# 11_ESP.net
KiCad netlist of a schematic drawn in EAGLE
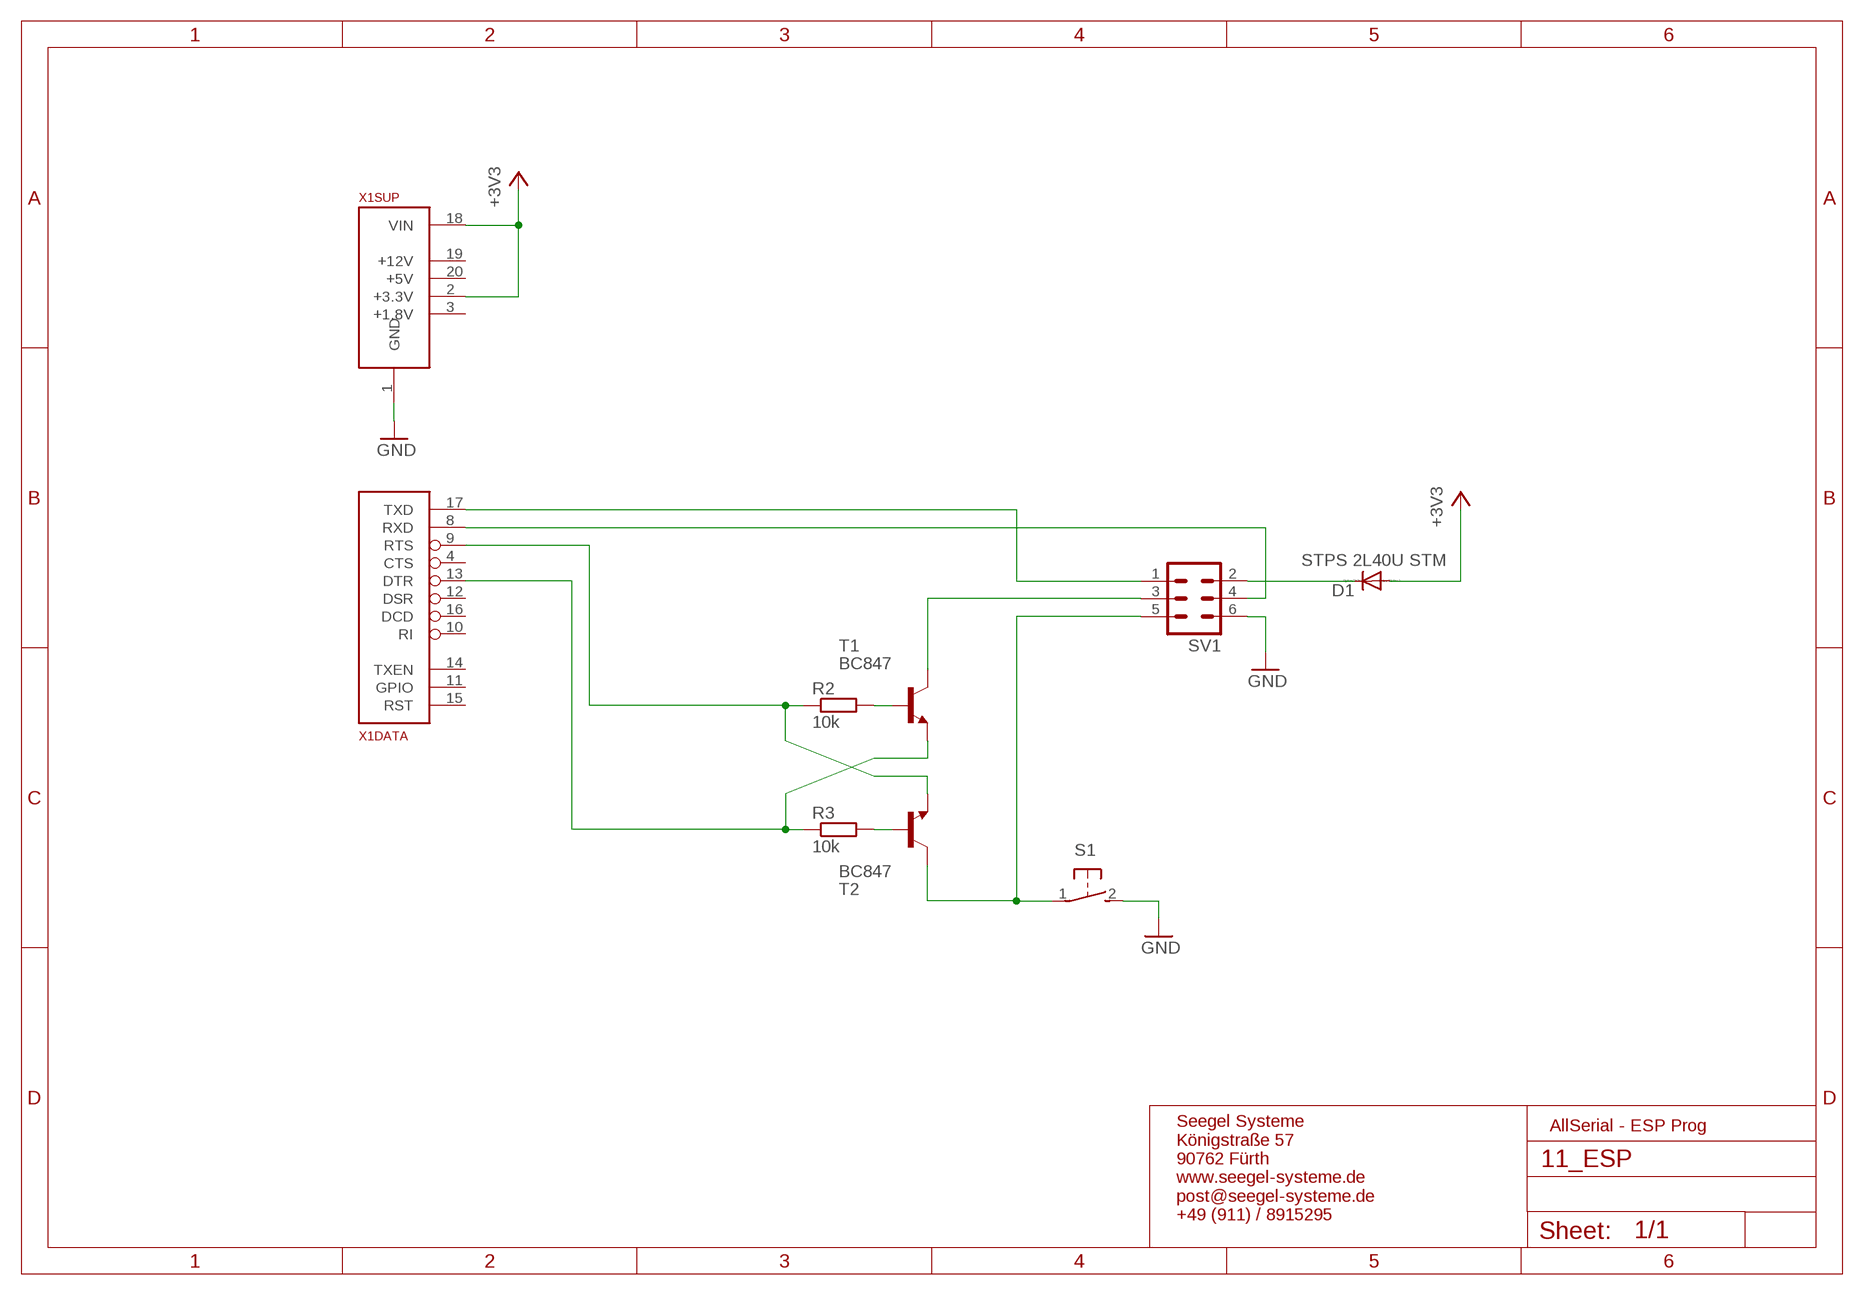
[diagram p0: schematic, sheet 1]

(export (version "E")
  (design (tool "Eeschema 10.0.6"))
  (components
    (comp (ref "D1")
      (value "STPS 2L40U STM")
      (footprint "eagle-import:DO214AA")
      (libsource (lib "eagle-import") (part "DIODE-DO214AA"))
    )
    (comp (ref "R2")
      (value "10k")
      (footprint "eagle-import:R0805")
      (libsource (lib "eagle-import") (part "R-EU_R0805"))
    )
    (comp (ref "R3")
      (value "10k")
      (footprint "eagle-import:R0805")
      (libsource (lib "eagle-import") (part "R-EU_R0805"))
    )
    (comp (ref "S1")
      (value "31-XX")
      (footprint "eagle-import:B3F-31XX")
      (fields (field (name "MPN") "B3F-3100"))
      (libsource (lib "eagle-import") (part "31-XX"))
    )
    (comp (ref "SV1")
      (value "ML6L")
      (footprint "eagle-import:ML6L")
      (libsource (lib "eagle-import") (part "ML6L"))
    )
    (comp (ref "T1")
      (value "BC847")
      (footprint "eagle-import:SOT23")
      (libsource (lib "eagle-import") (part "BC847"))
    )
    (comp (ref "T2")
      (value "BC847")
      (footprint "eagle-import:SOT23")
      (libsource (lib "eagle-import") (part "BC847"))
    )
    (comp (ref "X1")
      (value "ALLSERIALSLAVE")
      (footprint "eagle-import:DAUGHTER-THT")
      (libsource (lib "eagle-import") (part "ALLSERIALSLAVE"))
    )
  )
  (nets
    (net (code "1") (name "+3V3") (class "Default")
      (node (ref "D1") (pin "A") (pinfunction "A_A") (pintype "passive"))
      (node (ref "X1") (pin "18") (pinfunction "VIN_18") (pintype "bidirectional"))
      (node (ref "X1") (pin "2") (pinfunction "+3.3V_2") (pintype "bidirectional"))
    )
    (net (code "2") (name "GND") (class "Default")
      (node (ref "S1") (pin "2") (pinfunction "S_2") (pintype "passive"))
      (node (ref "SV1") (pin "6") (pinfunction "6_6") (pintype "passive"))
      (node (ref "X1") (pin "1") (pinfunction "GND_1") (pintype "bidirectional"))
    )
    (net (code "3") (name "Net-(D1-PadC)") (class "Default")
      (node (ref "D1") (pin "C") (pinfunction "C_C") (pintype "passive"))
      (node (ref "SV1") (pin "2") (pinfunction "2_2") (pintype "passive"))
    )
    (net (code "4") (name "Net-(S1-P)") (class "Default")
      (node (ref "S1") (pin "1") (pinfunction "P_1") (pintype "passive"))
      (node (ref "SV1") (pin "5") (pinfunction "5_5") (pintype "passive"))
      (node (ref "T2") (pin "3") (pinfunction "C_3") (pintype "passive"))
    )
    (net (code "5") (name "Net-(T1-B)") (class "Default")
      (node (ref "R2") (pin "2") (pinfunction "2_2") (pintype "passive"))
      (node (ref "T1") (pin "1") (pinfunction "B_1") (pintype "passive"))
    )
    (net (code "6") (name "Net-(T1-C)") (class "Default")
      (node (ref "SV1") (pin "3") (pinfunction "3_3") (pintype "passive"))
      (node (ref "T1") (pin "3") (pinfunction "C_3") (pintype "passive"))
    )
    (net (code "7") (name "Net-(T1-E)") (class "Default")
      (node (ref "R3") (pin "1") (pinfunction "1_1") (pintype "passive"))
      (node (ref "T1") (pin "2") (pinfunction "E_2") (pintype "passive"))
      (node (ref "X1") (pin "13") (pinfunction "DTR_13") (pintype "output"))
    )
    (net (code "8") (name "Net-(T2-B)") (class "Default")
      (node (ref "R3") (pin "2") (pinfunction "2_2") (pintype "passive"))
      (node (ref "T2") (pin "1") (pinfunction "B_1") (pintype "passive"))
    )
    (net (code "9") (name "Net-(T2-E)") (class "Default")
      (node (ref "R2") (pin "1") (pinfunction "1_1") (pintype "passive"))
      (node (ref "T2") (pin "2") (pinfunction "E_2") (pintype "passive"))
      (node (ref "X1") (pin "9") (pinfunction "RTS_9") (pintype "output"))
    )
    (net (code "10") (name "Net-(X1A-RXD)") (class "Default")
      (node (ref "SV1") (pin "4") (pinfunction "4_4") (pintype "passive"))
      (node (ref "X1") (pin "8") (pinfunction "RXD_8") (pintype "input"))
    )
    (net (code "11") (name "Net-(X1A-TXD)") (class "Default")
      (node (ref "SV1") (pin "1") (pinfunction "1_1") (pintype "passive"))
      (node (ref "X1") (pin "17") (pinfunction "TXD_17") (pintype "output"))
    )
    (net (code "12") (name "unconnected-(X1A-CTS-Pad4)") (class "Default")
      (node (ref "X1") (pin "4") (pinfunction "CTS_4") (pintype "input"))
    )
    (net (code "13") (name "unconnected-(X1A-DCD-Pad16)") (class "Default")
      (node (ref "X1") (pin "16") (pinfunction "DCD_16") (pintype "input"))
    )
    (net (code "14") (name "unconnected-(X1A-DSR-Pad12)") (class "Default")
      (node (ref "X1") (pin "12") (pinfunction "DSR_12") (pintype "input"))
    )
    (net (code "15") (name "unconnected-(X1A-GPIO-Pad11)") (class "Default")
      (node (ref "X1") (pin "11") (pinfunction "GPIO_11") (pintype "bidirectional"))
    )
    (net (code "16") (name "unconnected-(X1A-RI-Pad10)") (class "Default")
      (node (ref "X1") (pin "10") (pinfunction "RI_10") (pintype "input"))
    )
    (net (code "17") (name "unconnected-(X1A-RST-Pad15)") (class "Default")
      (node (ref "X1") (pin "15") (pinfunction "RST_15") (pintype "bidirectional"))
    )
    (net (code "18") (name "unconnected-(X1A-TXEN-Pad14)") (class "Default")
      (node (ref "X1") (pin "14") (pinfunction "TXEN_14") (pintype "output"))
    )
    (net (code "19") (name "unconnected-(X1B-+1.8V-Pad3)") (class "Default")
      (node (ref "X1") (pin "3") (pinfunction "+1.8V_3") (pintype "bidirectional"))
    )
    (net (code "20") (name "unconnected-(X1B-+5V-Pad20)") (class "Default")
      (node (ref "X1") (pin "20") (pinfunction "+5V_20") (pintype "bidirectional"))
    )
    (net (code "21") (name "unconnected-(X1B-+12V-Pad19)") (class "Default")
      (node (ref "X1") (pin "19") (pinfunction "+12V_19") (pintype "bidirectional"))
    )
  )
)
